# Analogread_final.net
KiCad netlist of a schematic drawn in Altium Designer
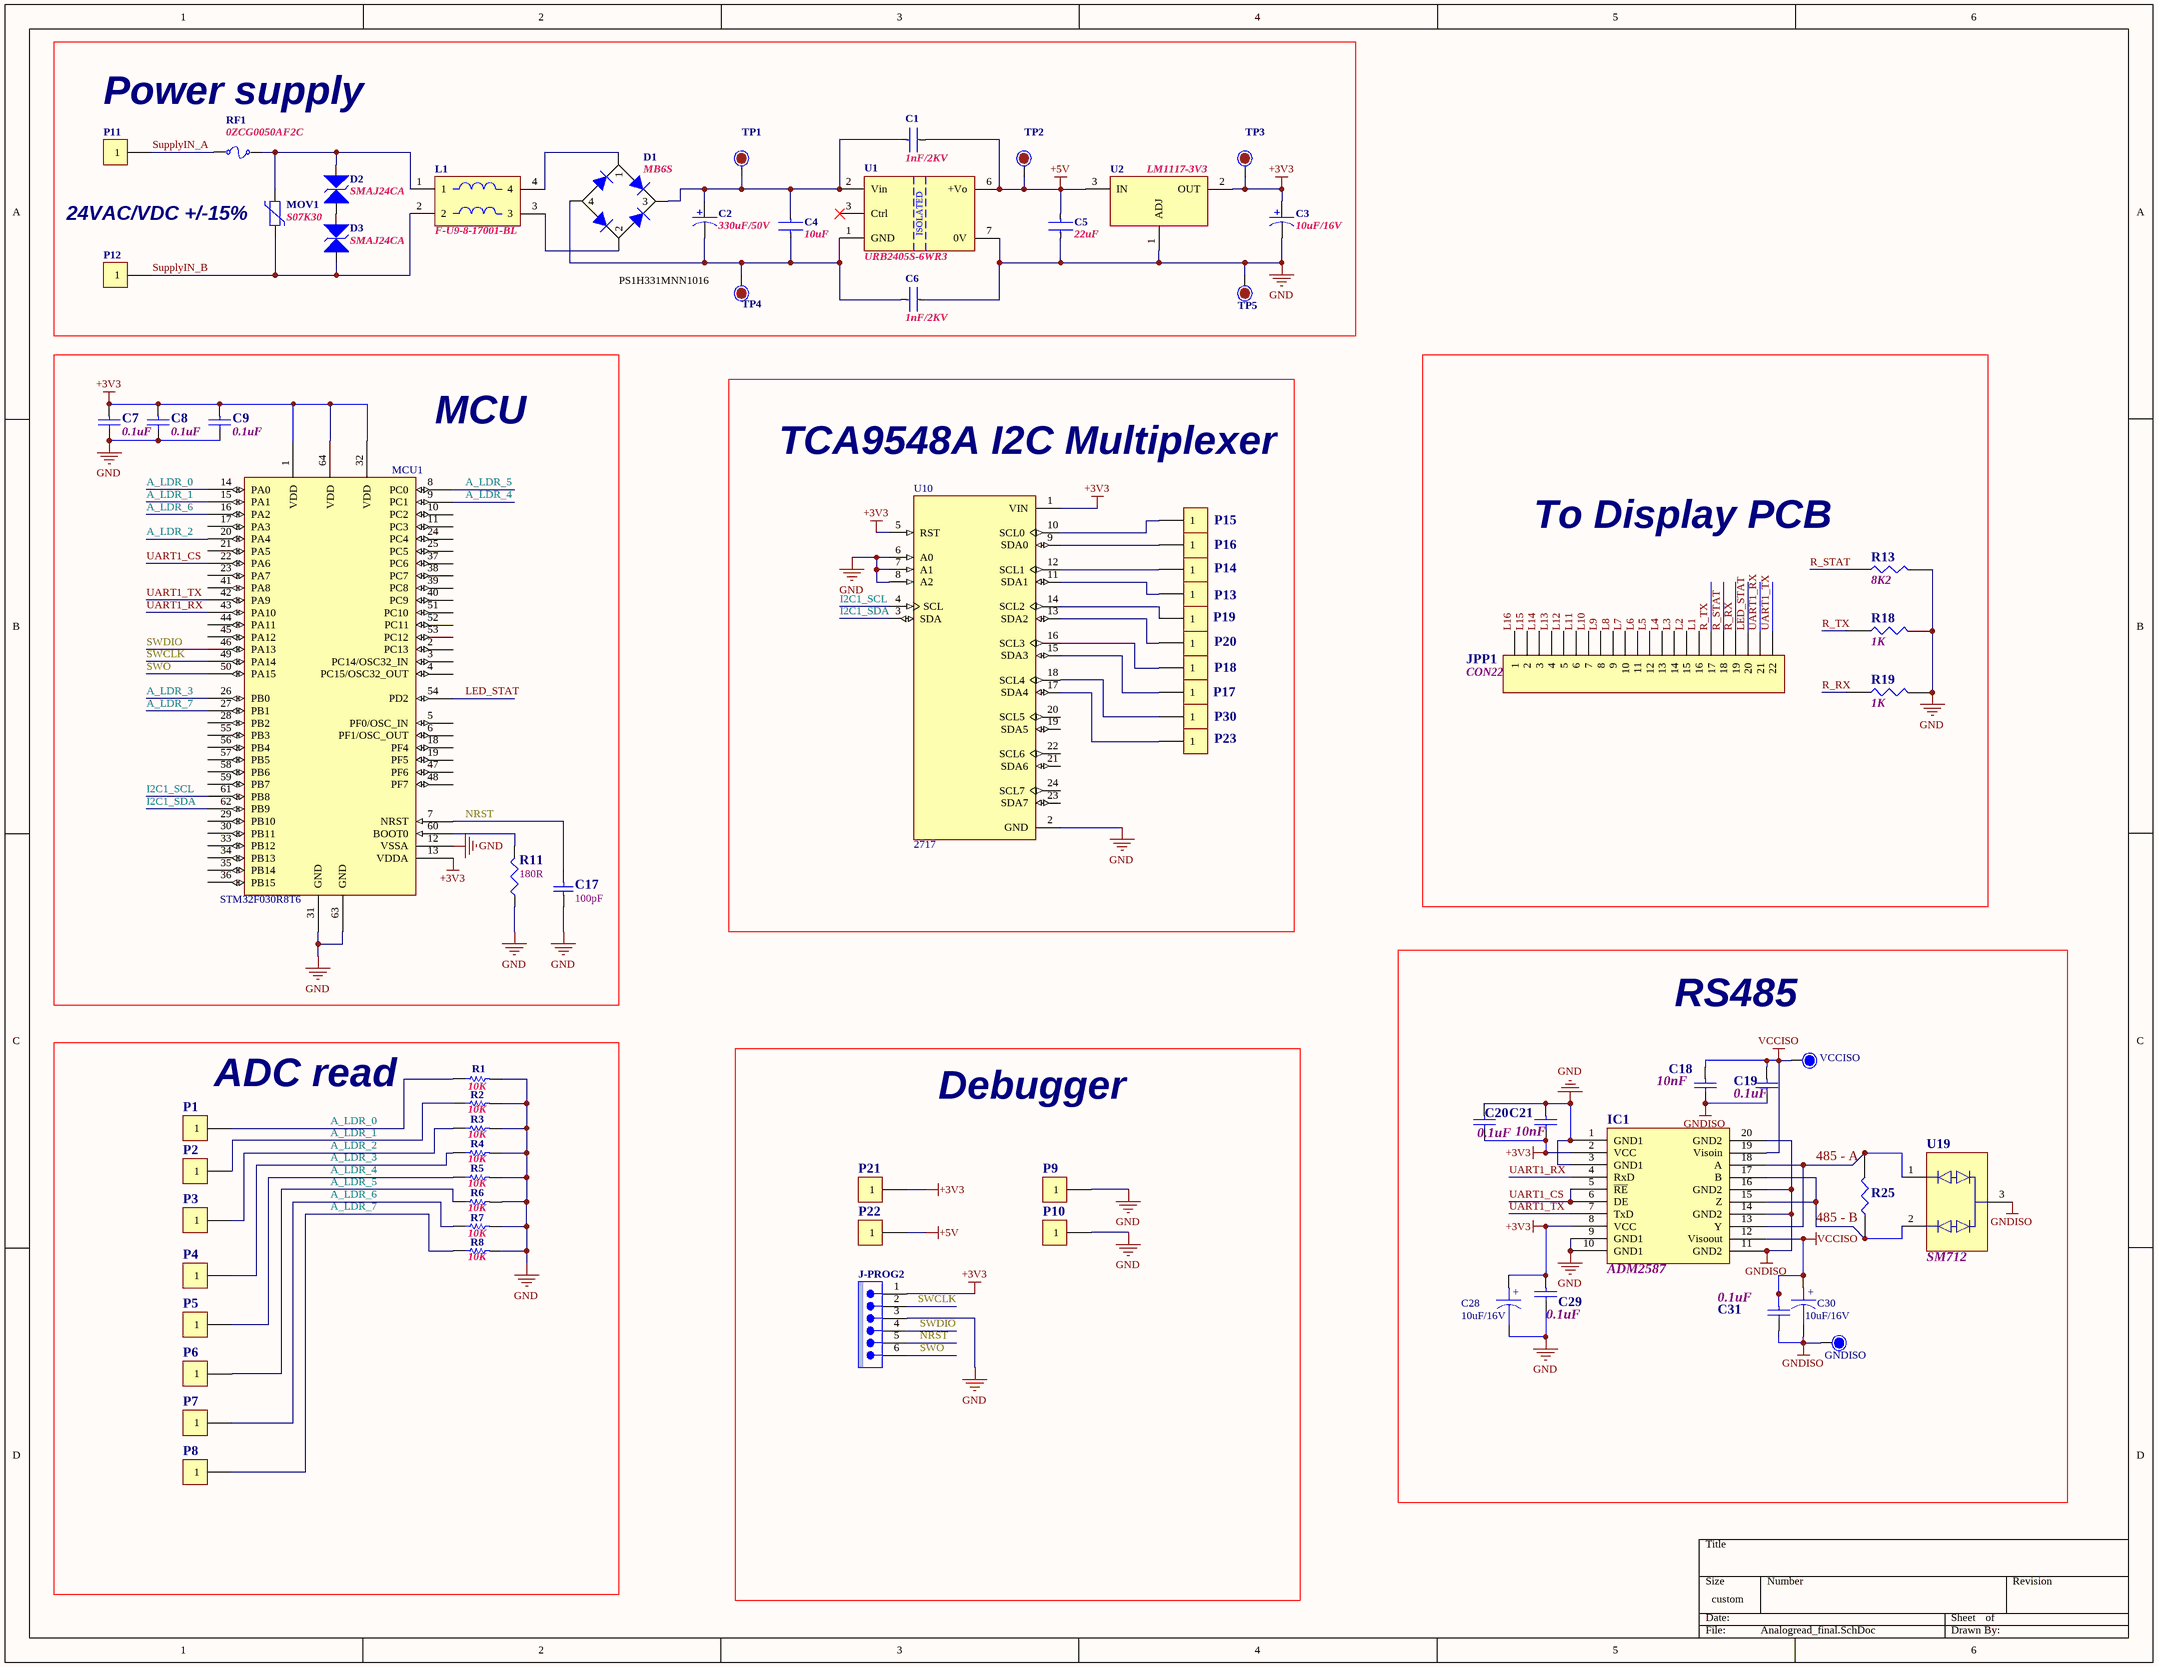
[diagram p0: Analogread_final.SchDoc]

(export (version "E")
  (design (tool "Eeschema 10.0.6"))
  (components
    (comp (ref "C1")
      (value "1nF/2KV")
      (footprint "CAPS0.3")
      (description "CAP CER, ?F, ?V, ?, THT 0.3\"")
      (libsource (lib "Primus") (part "CAP 0.3{dblquote} (THD)"))
    )
    (comp (ref "C2")
      (value "330uF/50V")
      (footprint "VER-D1000-H1250")
      (description "Aluminum Electrolytic Capacitor (Radial),\r\n?uF, ?V, Diameter 10mm")
      (libsource (lib "Primus") (part "CAP ELEC D10 (THD)"))
    )
    (comp (ref "C3")
      (value "10uF/16V")
      (footprint "CAPMP3528")
      (description "CAP TANTALUM, ?uF, ?V, 1411")
      (libsource (lib "Primus") (part "CAP TANTALUM (SMD)"))
    )
    (comp (ref "C4")
      (value "10uF")
      (footprint "CAPC2013 (0805)")
      (description "CAP CER, ?F, ?V, ±?%, 2013 (0805)")
      (libsource (lib "Primus") (part "CAP CHIP 0805 (SMD)"))
    )
    (comp (ref "C5")
      (value "22uF")
      (footprint "CAPC2013 (0805)")
      (description "CAP CER, ?F, ?V, ±?%, 2013 (0805)")
      (libsource (lib "Primus") (part "CAP CHIP 0805 (SMD)"))
    )
    (comp (ref "C6")
      (value "1nF/2KV")
      (footprint "CAPS0.3")
      (description "CAP CER, ?F, ?V, ?, THT 0.3\"")
      (libsource (lib "Primus") (part "CAP 0.3{dblquote} (THD)"))
    )
    (comp (ref "C7")
      (value "0.1uF")
      (footprint "CAPC1608 (0603)")
      (description "Capacitor")
      (libsource (lib "*") (part "CAP"))
    )
    (comp (ref "C8")
      (value "0.1uF")
      (footprint "CAPC1608 (0603)")
      (description "Capacitor")
      (libsource (lib "*") (part "CAP"))
    )
    (comp (ref "C9")
      (value "0.1uF")
      (footprint "CAPC1608 (0603)")
      (description "Capacitor")
      (libsource (lib "*") (part "CAP"))
    )
    (comp (ref "C17")
      (value "100pF")
      (footprint "CAPC1608 (0603)")
      (description "Capacitor")
      (fields (field (name "PUBLISHER") "Altium Limited"))
      (libsource (lib "*") (part "Cap"))
    )
    (comp (ref "C18")
      (value "10nF")
      (footprint "0805")
      (description "Capacitor")
      (libsource (lib "*") (part "CAP"))
    )
    (comp (ref "C19")
      (value "0.1uF")
      (footprint "CAPC1608 (0603)")
      (description "Capacitor")
      (libsource (lib "*") (part "CAP"))
    )
    (comp (ref "C20")
      (value "0.1uF")
      (footprint "CAPC1608 (0603)")
      (description "Capacitor")
      (libsource (lib "*") (part "CAP"))
    )
    (comp (ref "C21")
      (value "10nF")
      (footprint "0805")
      (description "Capacitor")
      (libsource (lib "*") (part "CAP"))
    )
    (comp (ref "C28")
      (value "10uF/16V")
      (footprint "CAPMP3528")
      (description "Capacitor")
      (libsource (lib "*") (part "CAPACITOR POL"))
    )
    (comp (ref "C29")
      (value "0.1uF")
      (footprint "CAPC1608 (0603)")
      (description "Capacitor")
      (libsource (lib "*") (part "CAP"))
    )
    (comp (ref "C30")
      (value "10uF/16V")
      (footprint "CAPMP3528")
      (description "Capacitor")
      (libsource (lib "*") (part "CAPACITOR POL"))
    )
    (comp (ref "C31")
      (value "0.1uF")
      (footprint "CAPC1608 (0603)")
      (description "Capacitor")
      (libsource (lib "*") (part "CAP"))
    )
    (comp (ref "D1") (value "MB6S") (footprint "MB6S") (libsource (lib "Primus") (part "MB6S")))
    (comp (ref "D2")
      (value "SMAJ24CA")
      (footprint "SMA-(DO-214AC)")
      (libsource (lib "Primus") (part "DIODE TVS BI-DIR"))
    )
    (comp (ref "D3")
      (value "SMAJ24CA")
      (footprint "SMA-(DO-214AC)")
      (libsource (lib "Primus") (part "DIODE TVS BI-DIR"))
    )
    (comp (ref "IC1")
      (value "ADM2587")
      (footprint "SOIC-20")
      (description "Transceiver with ±15 kV ESD Protection")
      (libsource (lib "Primus") (part "ADM2582E"))
    )
    (comp (ref "J-PROG2")
      (value "PIN HEADER 1x6")
      (footprint "PIN-HEADER 2.54 1x6")
      (libsource (lib "Primus") (part "PIN HEADER 1x6"))
    )
    (comp (ref "JPP1") (value "CON22") (footprint "JUMPER22") (libsource (lib "*") (part "CON22")))
    (comp (ref "L1")
      (value "F-U9-8-17001-BL")
      (footprint "BT-1720")
      (libsource (lib "Primus") (part "F-U9-8-17001-BL"))
    )
    (comp (ref "MCU1")
      (value "STM32F030R8T6")
      (footprint "QFP64 [10x10]")
      (libsource (lib "Primus") (part "STM32F030R8T6"))
    )
    (comp (ref "MOV1")
      (value "S07K30")
      (footprint "VARISTER(7MM)")
      (description "Disc Varistor 7mm")
      (libsource (lib "Primus") (part "Varistor D7"))
    )
    (comp (ref "P1")
      (value "CON1")
      (footprint "PAD_B3")
      (description "Connector")
      (libsource (lib "") (part "CON1_1"))
    )
    (comp (ref "P2")
      (value "CON1")
      (footprint "PAD_B3")
      (description "Connector")
      (libsource (lib "") (part "CON1_1"))
    )
    (comp (ref "P3")
      (value "CON1")
      (footprint "PAD_B3")
      (description "Connector")
      (libsource (lib "") (part "CON1_1"))
    )
    (comp (ref "P4")
      (value "CON1")
      (footprint "PAD_B3")
      (description "Connector")
      (libsource (lib "") (part "CON1_1"))
    )
    (comp (ref "P5")
      (value "CON1")
      (footprint "PAD_B3")
      (description "Connector")
      (libsource (lib "") (part "CON1_1"))
    )
    (comp (ref "P6")
      (value "CON1")
      (footprint "PAD_B3")
      (description "Connector")
      (libsource (lib "") (part "CON1_1"))
    )
    (comp (ref "P7")
      (value "CON1")
      (footprint "PAD_B3")
      (description "Connector")
      (libsource (lib "") (part "CON1_1"))
    )
    (comp (ref "P8")
      (value "CON1")
      (footprint "PAD_B3")
      (description "Connector")
      (libsource (lib "") (part "CON1_1"))
    )
    (comp (ref "P9")
      (value "CON1")
      (footprint "PAD_B3")
      (description "Connector")
      (libsource (lib "") (part "CON1_1"))
    )
    (comp (ref "P10")
      (value "CON1")
      (footprint "PAD_B3")
      (description "Connector")
      (libsource (lib "") (part "CON1_1"))
    )
    (comp (ref "P11") (value "1-PAD THT") (footprint "PAD-B3") (libsource (lib "Primus") (part "1-PAD THT")))
    (comp (ref "P12") (value "1-PAD THT") (footprint "PAD-B3") (libsource (lib "Primus") (part "1-PAD THT")))
    (comp (ref "P13")
      (value "CON1")
      (footprint "PAD_B3")
      (description "Connector")
      (libsource (lib "*") (part "CON1"))
    )
    (comp (ref "P14")
      (value "CON1")
      (footprint "PAD_B3")
      (description "Connector")
      (libsource (lib "*") (part "CON1"))
    )
    (comp (ref "P15")
      (value "CON1")
      (footprint "PAD_B3")
      (description "Connector")
      (libsource (lib "*") (part "CON1"))
    )
    (comp (ref "P16")
      (value "CON1")
      (footprint "PAD_B3")
      (description "Connector")
      (libsource (lib "*") (part "CON1"))
    )
    (comp (ref "P17")
      (value "CON1")
      (footprint "PAD_B3")
      (description "Connector")
      (libsource (lib "*") (part "CON1"))
    )
    (comp (ref "P18")
      (value "CON1")
      (footprint "PAD_B3")
      (description "Connector")
      (libsource (lib "*") (part "CON1"))
    )
    (comp (ref "P19")
      (value "CON1")
      (footprint "PAD_B3")
      (description "Connector")
      (libsource (lib "*") (part "CON1"))
    )
    (comp (ref "P20")
      (value "CON1")
      (footprint "PAD_B3")
      (description "Connector")
      (libsource (lib "*") (part "CON1"))
    )
    (comp (ref "P21")
      (value "CON1")
      (footprint "PAD_B3")
      (description "Connector")
      (libsource (lib "") (part "CON1_1"))
    )
    (comp (ref "P22")
      (value "CON1")
      (footprint "PAD_B3")
      (description "Connector")
      (libsource (lib "") (part "CON1_1"))
    )
    (comp (ref "P23")
      (value "CON1")
      (footprint "PAD_B3")
      (description "Connector")
      (libsource (lib "*") (part "CON1"))
    )
    (comp (ref "P30")
      (value "CON1")
      (footprint "PAD_B3")
      (description "Connector")
      (libsource (lib "*") (part "CON1"))
    )
    (comp (ref "R1")
      (value "10K")
      (footprint "RESC1608 (0603)")
      (description "Chip Resistor, ? Ohm, +/-?%, ?W, 1608 (0603)")
      (libsource (lib "Primus") (part "RES CHIP 0603 (SMD)"))
    )
    (comp (ref "R2")
      (value "10K")
      (footprint "RESC1608 (0603)")
      (description "Chip Resistor, ? Ohm, +/-?%, ?W, 1608 (0603)")
      (libsource (lib "Primus") (part "RES CHIP 0603 (SMD)"))
    )
    (comp (ref "R3")
      (value "10K")
      (footprint "RESC1608 (0603)")
      (description "Chip Resistor, ? Ohm, +/-?%, ?W, 1608 (0603)")
      (libsource (lib "Primus") (part "RES CHIP 0603 (SMD)"))
    )
    (comp (ref "R4")
      (value "10K")
      (footprint "RESC1608 (0603)")
      (description "Chip Resistor, ? Ohm, +/-?%, ?W, 1608 (0603)")
      (libsource (lib "Primus") (part "RES CHIP 0603 (SMD)"))
    )
    (comp (ref "R5")
      (value "10K")
      (footprint "RESC1608 (0603)")
      (description "Chip Resistor, ? Ohm, +/-?%, ?W, 1608 (0603)")
      (libsource (lib "Primus") (part "RES CHIP 0603 (SMD)"))
    )
    (comp (ref "R6")
      (value "10K")
      (footprint "RESC1608 (0603)")
      (description "Chip Resistor, ? Ohm, +/-?%, ?W, 1608 (0603)")
      (libsource (lib "Primus") (part "RES CHIP 0603 (SMD)"))
    )
    (comp (ref "R7")
      (value "10K")
      (footprint "RESC1608 (0603)")
      (description "Chip Resistor, ? Ohm, +/-?%, ?W, 1608 (0603)")
      (libsource (lib "Primus") (part "RES CHIP 0603 (SMD)"))
    )
    (comp (ref "R8")
      (value "10K")
      (footprint "RESC1608 (0603)")
      (description "Chip Resistor, ? Ohm, +/-?%, ?W, 1608 (0603)")
      (libsource (lib "Primus") (part "RES CHIP 0603 (SMD)"))
    )
    (comp (ref "R11")
      (value "180R")
      (footprint "0805")
      (description "Resistor")
      (fields (field (name "PUBLISHER") "Altium Limited"))
      (libsource (lib "*") (part "Res3"))
    )
    (comp (ref "R13") (value "8K2") (footprint "RESC1608 (0603)") (libsource (lib "*") (part "RES1")))
    (comp (ref "R18") (value "1K") (footprint "RESC1608 (0603)") (libsource (lib "*") (part "RES1")))
    (comp (ref "R19") (value "1K") (footprint "RESC1608 (0603)") (libsource (lib "*") (part "RES1")))
    (comp (ref "R25") (value "~") (footprint "0805") (libsource (lib "*") (part "RES1")))
    (comp (ref "RF1")
      (value "0ZCG0050AF2C")
      (footprint "0ZCGXXXXXXXX")
      (description "Polymeric PTC Resettable Fuse 30V 500 mA Ih Surface Mount 1812 (4532 Metric), Concave")
      (libsource (lib "Primus") (part "0ZCG0050AF2C"))
    )
    (comp (ref "TP1")
      (value "+VIN")
      (footprint "TP1-1.2mm")
      (description "TEST PAD")
      (libsource (lib "Primus") (part "TP"))
    )
    (comp (ref "TP2")
      (value "+5V")
      (footprint "TP1-1.2mm")
      (description "TEST PAD")
      (libsource (lib "Primus") (part "TP"))
    )
    (comp (ref "TP3")
      (value "+3V3")
      (footprint "TP1-1.2mm")
      (description "TEST PAD")
      (libsource (lib "Primus") (part "TP"))
    )
    (comp (ref "TP4")
      (value "G_VIN")
      (footprint "TP1-1.2mm")
      (description "TEST PAD")
      (libsource (lib "Primus") (part "TP"))
    )
    (comp (ref "TP5")
      (value "GND")
      (footprint "TP1-1.2mm")
      (description "TEST PAD")
      (libsource (lib "Primus") (part "TP"))
    )
    (comp (ref "TP6")
      (value "VCCISO")
      (footprint "TP1-1.2mm")
      (description "TEST PAD")
      (libsource (lib "Primus") (part "TP"))
    )
    (comp (ref "TP7")
      (value "GNDISO")
      (footprint "TP1-1.2mm")
      (description "TEST PAD")
      (libsource (lib "Primus") (part "TP"))
    )
    (comp (ref "U1")
      (value "URB2405S-6WR3")
      (footprint "URBxxxxS-6WR3")
      (description "6W, Regulated, Isolated, DC to DC Converter,\r\n24V to 5V@1200mA")
      (libsource (lib "Primus") (part "URB2405S-6WR3"))
    )
    (comp (ref "U2")
      (value "LM1117-3V3")
      (footprint "SOT-223")
      (description "Low-Dropout Linear Regulator 800 mA")
      (libsource (lib "Primus") (part "LM1117-3V3"))
    )
    (comp (ref "U10")
      (value "2717")
      (footprint "MODULE_2717")
      (description "Module: multiplexer; I2C interface multiplexer; TCA9548A; 3Ã·5VDC")
      (fields (field (name "MF") "Adafruit"))
      (libsource (lib "2717") (part "2717"))
    )
    (comp (ref "U19") (value "SM712") (footprint "SOT-23-3") (libsource (lib "*") (part "SM712")))
  )
  (nets
    (net (code "1") (name "+3V3") (class "Default")
      (node (ref "C20") (pin "2") (pinfunction "2_2") (pintype "passive"))
      (node (ref "C21") (pin "2") (pinfunction "2_2") (pintype "passive"))
      (node (ref "C28") (pin "1") (pinfunction "1_1") (pintype "passive"))
      (node (ref "C29") (pin "1") (pinfunction "1_1") (pintype "passive"))
      (node (ref "C3") (pin "1") (pinfunction "1_1") (pintype "passive"))
      (node (ref "C7") (pin "1") (pinfunction "1_1") (pintype "passive"))
      (node (ref "C8") (pin "1") (pinfunction "1_1") (pintype "passive"))
      (node (ref "C9") (pin "1") (pinfunction "1_1") (pintype "passive"))
      (node (ref "IC1") (pin "2") (pinfunction "VCC_2") (pintype "passive"))
      (node (ref "IC1") (pin "8") (pinfunction "VCC_8") (pintype "passive"))
      (node (ref "J-PROG2") (pin "1") (pinfunction "1_1") (pintype "passive"))
      (node (ref "MCU1") (pin "1") (pinfunction "VDD_1") (pintype "passive"))
      (node (ref "MCU1") (pin "13") (pinfunction "VDDA_13") (pintype "power_in"))
      (node (ref "MCU1") (pin "32") (pinfunction "VDD_32") (pintype "passive"))
      (node (ref "MCU1") (pin "64") (pinfunction "VDD_64") (pintype "passive"))
      (node (ref "P21") (pin "1") (pinfunction "1_1") (pintype "passive"))
      (node (ref "TP3") (pin "TP") (pinfunction "Test_point_TP") (pintype "passive"))
      (node (ref "U10") (pin "1") (pinfunction "VIN_1") (pintype "power_in"))
      (node (ref "U10") (pin "5") (pinfunction "RST_5") (pintype "input"))
      (node (ref "U2") (pin "2") (pinfunction "OUT_2") (pintype "passive"))
    )
    (net (code "2") (name "+5V") (class "Default")
      (node (ref "C1") (pin "2") (pinfunction "2_2") (pintype "passive"))
      (node (ref "C5") (pin "2") (pinfunction "2_2") (pintype "passive"))
      (node (ref "P22") (pin "1") (pinfunction "1_1") (pintype "passive"))
      (node (ref "TP2") (pin "TP") (pinfunction "Test_point_TP") (pintype "passive"))
      (node (ref "U1") (pin "6") (pinfunction "+Vo_6") (pintype "passive"))
      (node (ref "U2") (pin "3") (pinfunction "IN_3") (pintype "passive"))
    )
    (net (code "3") (name "/485 - A") (class "Default")
      (node (ref "IC1") (pin "13") (pinfunction "Y_13") (pintype "passive"))
      (node (ref "IC1") (pin "18") (pinfunction "A_18") (pintype "passive"))
      (node (ref "R25") (pin "2") (pinfunction "2_2") (pintype "passive"))
      (node (ref "U19") (pin "1") (pinfunction "1_1") (pintype "passive"))
    )
    (net (code "4") (name "/485 - B") (class "Default")
      (node (ref "IC1") (pin "15") (pinfunction "Z_15") (pintype "passive"))
      (node (ref "IC1") (pin "17") (pinfunction "B_17") (pintype "passive"))
      (node (ref "R25") (pin "1") (pinfunction "1_1") (pintype "passive"))
      (node (ref "U19") (pin "2") (pinfunction "2_2") (pintype "passive"))
    )
    (net (code "5") (name "/A_LDR_0") (class "Default")
      (node (ref "MCU1") (pin "14") (pinfunction "PA0_14") (pintype "bidirectional"))
      (node (ref "P1") (pin "1") (pinfunction "1_1") (pintype "passive"))
      (node (ref "R1") (pin "2") (pinfunction "13_2") (pintype "passive"))
    )
    (net (code "6") (name "/A_LDR_1") (class "Default")
      (node (ref "MCU1") (pin "15") (pinfunction "PA1_15") (pintype "bidirectional"))
      (node (ref "P2") (pin "1") (pinfunction "1_1") (pintype "passive"))
      (node (ref "R2") (pin "2") (pinfunction "13_2") (pintype "passive"))
    )
    (net (code "7") (name "/A_LDR_2") (class "Default")
      (node (ref "MCU1") (pin "20") (pinfunction "PA4_20") (pintype "bidirectional"))
      (node (ref "P3") (pin "1") (pinfunction "1_1") (pintype "passive"))
      (node (ref "R3") (pin "2") (pinfunction "13_2") (pintype "passive"))
    )
    (net (code "8") (name "/A_LDR_3") (class "Default")
      (node (ref "MCU1") (pin "26") (pinfunction "PB0_26") (pintype "bidirectional"))
      (node (ref "P4") (pin "1") (pinfunction "1_1") (pintype "passive"))
      (node (ref "R4") (pin "2") (pinfunction "13_2") (pintype "passive"))
    )
    (net (code "9") (name "/A_LDR_4") (class "Default")
      (node (ref "MCU1") (pin "9") (pinfunction "PC1_9") (pintype "bidirectional"))
      (node (ref "P5") (pin "1") (pinfunction "1_1") (pintype "passive"))
      (node (ref "R5") (pin "2") (pinfunction "13_2") (pintype "passive"))
    )
    (net (code "10") (name "/A_LDR_5") (class "Default")
      (node (ref "MCU1") (pin "8") (pinfunction "PC0_8") (pintype "bidirectional"))
      (node (ref "P6") (pin "1") (pinfunction "1_1") (pintype "passive"))
      (node (ref "R6") (pin "2") (pinfunction "13_2") (pintype "passive"))
    )
    (net (code "11") (name "/A_LDR_6") (class "Default")
      (node (ref "MCU1") (pin "16") (pinfunction "PA2_16") (pintype "bidirectional"))
      (node (ref "P7") (pin "1") (pinfunction "1_1") (pintype "passive"))
      (node (ref "R7") (pin "2") (pinfunction "13_2") (pintype "passive"))
    )
    (net (code "12") (name "/A_LDR_7") (class "Default")
      (node (ref "MCU1") (pin "27") (pinfunction "PB1_27") (pintype "bidirectional"))
      (node (ref "P8") (pin "1") (pinfunction "1_1") (pintype "passive"))
      (node (ref "R8") (pin "2") (pinfunction "13_2") (pintype "passive"))
    )
    (net (code "13") (name "/I2C1_SCL") (class "Default")
      (node (ref "MCU1") (pin "61") (pinfunction "PB8_61") (pintype "bidirectional"))
      (node (ref "U10") (pin "4") (pinfunction "SCL_4") (pintype "input"))
    )
    (net (code "14") (name "/I2C1_SDA") (class "Default")
      (node (ref "MCU1") (pin "62") (pinfunction "PB9_62") (pintype "bidirectional"))
      (node (ref "U10") (pin "3") (pinfunction "SDA_3") (pintype "bidirectional"))
    )
    (net (code "15") (name "/L1") (class "Default")
      (node (ref "JPP1") (pin "16") (pinfunction "16_16") (pintype "passive"))
    )
    (net (code "16") (name "/L2") (class "Default")
      (node (ref "JPP1") (pin "15") (pinfunction "15_15") (pintype "passive"))
    )
    (net (code "17") (name "/L3") (class "Default")
      (node (ref "JPP1") (pin "14") (pinfunction "14_14") (pintype "passive"))
    )
    (net (code "18") (name "/L4") (class "Default")
      (node (ref "JPP1") (pin "13") (pinfunction "13_13") (pintype "passive"))
    )
    (net (code "19") (name "/L5") (class "Default")
      (node (ref "JPP1") (pin "12") (pinfunction "12_12") (pintype "passive"))
    )
    (net (code "20") (name "/L6") (class "Default")
      (node (ref "JPP1") (pin "11") (pinfunction "11_11") (pintype "passive"))
    )
    (net (code "21") (name "/L7") (class "Default")
      (node (ref "JPP1") (pin "10") (pinfunction "10_10") (pintype "passive"))
    )
    (net (code "22") (name "/L8") (class "Default")
      (node (ref "JPP1") (pin "9") (pinfunction "9_9") (pintype "passive"))
    )
    (net (code "23") (name "/L9") (class "Default")
      (node (ref "JPP1") (pin "8") (pinfunction "8_8") (pintype "passive"))
    )
    (net (code "24") (name "/L10") (class "Default")
      (node (ref "JPP1") (pin "7") (pinfunction "7_7") (pintype "passive"))
    )
    (net (code "25") (name "/L11") (class "Default")
      (node (ref "JPP1") (pin "6") (pinfunction "6_6") (pintype "passive"))
    )
    (net (code "26") (name "/L12") (class "Default")
      (node (ref "JPP1") (pin "5") (pinfunction "5_5") (pintype "passive"))
    )
    (net (code "27") (name "/L13") (class "Default")
      (node (ref "JPP1") (pin "4") (pinfunction "4_4") (pintype "passive"))
    )
    (net (code "28") (name "/L14") (class "Default")
      (node (ref "JPP1") (pin "3") (pinfunction "3_3") (pintype "passive"))
    )
    (net (code "29") (name "/L15") (class "Default")
      (node (ref "JPP1") (pin "2") (pinfunction "2_2") (pintype "passive"))
    )
    (net (code "30") (name "/L16") (class "Default")
      (node (ref "JPP1") (pin "1") (pinfunction "1_1") (pintype "passive"))
    )
    (net (code "31") (name "/LED_STAT") (class "Default")
      (node (ref "JPP1") (pin "20") (pinfunction "20_20") (pintype "passive"))
      (node (ref "MCU1") (pin "54") (pinfunction "PD2_54") (pintype "bidirectional"))
    )
    (net (code "32") (name "/NRST") (class "Default")
      (node (ref "C17") (pin "2") (pinfunction "2_2") (pintype "passive"))
      (node (ref "J-PROG2") (pin "5") (pinfunction "5_5") (pintype "passive"))
      (node (ref "MCU1") (pin "7") (pinfunction "NRST_7") (pintype "input"))
    )
    (net (code "33") (name "/R_RX") (class "Default")
      (node (ref "JPP1") (pin "19") (pinfunction "19_19") (pintype "passive"))
      (node (ref "R19") (pin "1") (pinfunction "1_1") (pintype "passive"))
    )
    (net (code "34") (name "/R_STAT") (class "Default")
      (node (ref "JPP1") (pin "18") (pinfunction "18_18") (pintype "passive"))
      (node (ref "R13") (pin "1") (pinfunction "1_1") (pintype "passive"))
    )
    (net (code "35") (name "/R_TX") (class "Default")
      (node (ref "JPP1") (pin "17") (pinfunction "17_17") (pintype "passive"))
      (node (ref "R18") (pin "1") (pinfunction "1_1") (pintype "passive"))
    )
    (net (code "36") (name "/SWCLK") (class "Default")
      (node (ref "J-PROG2") (pin "2") (pinfunction "2_2") (pintype "passive"))
      (node (ref "MCU1") (pin "49") (pinfunction "PA14_49") (pintype "bidirectional"))
    )
    (net (code "37") (name "/SWDIO") (class "Default")
      (node (ref "J-PROG2") (pin "4") (pinfunction "4_4") (pintype "passive"))
      (node (ref "MCU1") (pin "46") (pinfunction "PA13_46") (pintype "bidirectional"))
    )
    (net (code "38") (name "/SWO") (class "Default")
      (node (ref "J-PROG2") (pin "6") (pinfunction "6_6") (pintype "passive"))
      (node (ref "MCU1") (pin "50") (pinfunction "PA15_50") (pintype "bidirectional"))
    )
    (net (code "39") (name "/SupplyIN_A") (class "Default")
      (node (ref "P11") (pin "1") (pinfunction "1_1") (pintype "passive"))
      (node (ref "RF1") (pin "1") (pinfunction "1_1") (pintype "passive"))
    )
    (net (code "40") (name "/SupplyIN_B") (class "Default")
      (node (ref "D3") (pin "A") (pinfunction "A_A") (pintype "passive"))
      (node (ref "L1") (pin "2") (pinfunction "2_2") (pintype "passive"))
      (node (ref "MOV1") (pin "2") (pinfunction "2_2") (pintype "passive"))
      (node (ref "P12") (pin "1") (pinfunction "1_1") (pintype "passive"))
    )
    (net (code "41") (name "/UART1_CS") (class "Default")
      (node (ref "IC1") (pin "5") (pinfunction "~{RE}_5") (pintype "passive"))
      (node (ref "IC1") (pin "6") (pinfunction "DE_6") (pintype "passive"))
      (node (ref "MCU1") (pin "22") (pinfunction "PA6_22") (pintype "bidirectional"))
    )
    (net (code "42") (name "/UART1_RX") (class "Default")
      (node (ref "IC1") (pin "4") (pinfunction "RxD_4") (pintype "passive"))
      (node (ref "JPP1") (pin "21") (pinfunction "21_21") (pintype "passive"))
      (node (ref "MCU1") (pin "43") (pinfunction "PA10_43") (pintype "bidirectional"))
    )
    (net (code "43") (name "/UART1_TX") (class "Default")
      (node (ref "IC1") (pin "7") (pinfunction "TxD_7") (pintype "passive"))
      (node (ref "JPP1") (pin "22") (pinfunction "22_22") (pintype "passive"))
      (node (ref "MCU1") (pin "42") (pinfunction "PA9_42") (pintype "bidirectional"))
    )
    (net (code "44") (name "GND") (class "Default")
      (node (ref "C17") (pin "1") (pinfunction "1_1") (pintype "passive"))
      (node (ref "C20") (pin "1") (pinfunction "1_1") (pintype "passive"))
      (node (ref "C21") (pin "1") (pinfunction "1_1") (pintype "passive"))
      (node (ref "C28") (pin "2") (pinfunction "2_2") (pintype "passive"))
      (node (ref "C29") (pin "2") (pinfunction "2_2") (pintype "passive"))
      (node (ref "C3") (pin "2") (pinfunction "2_2") (pintype "passive"))
      (node (ref "C5") (pin "1") (pinfunction "1_1") (pintype "passive"))
      (node (ref "C6") (pin "2") (pinfunction "2_2") (pintype "passive"))
      (node (ref "C7") (pin "2") (pinfunction "2_2") (pintype "passive"))
      (node (ref "C8") (pin "2") (pinfunction "2_2") (pintype "passive"))
      (node (ref "C9") (pin "2") (pinfunction "2_2") (pintype "passive"))
      (node (ref "IC1") (pin "1") (pinfunction "GND1_1") (pintype "passive"))
      (node (ref "IC1") (pin "10") (pinfunction "GND1_10") (pintype "passive"))
      (node (ref "IC1") (pin "3") (pinfunction "GND1_3") (pintype "passive"))
      (node (ref "IC1") (pin "9") (pinfunction "GND1_9") (pintype "passive"))
      (node (ref "J-PROG2") (pin "3") (pinfunction "3_3") (pintype "passive"))
      (node (ref "MCU1") (pin "12") (pinfunction "VSSA_12") (pintype "power_in"))
      (node (ref "MCU1") (pin "31") (pinfunction "GND_31") (pintype "passive"))
      (node (ref "MCU1") (pin "63") (pinfunction "GND_63") (pintype "passive"))
      (node (ref "P10") (pin "1") (pinfunction "1_1") (pintype "passive"))
      (node (ref "P9") (pin "1") (pinfunction "1_1") (pintype "passive"))
      (node (ref "R1") (pin "1") (pinfunction "12_1") (pintype "passive"))
      (node (ref "R11") (pin "1") (pinfunction "1_1") (pintype "passive"))
      (node (ref "R13") (pin "2") (pinfunction "2_2") (pintype "passive"))
      (node (ref "R18") (pin "2") (pinfunction "2_2") (pintype "passive"))
      (node (ref "R19") (pin "2") (pinfunction "2_2") (pintype "passive"))
      (node (ref "R2") (pin "1") (pinfunction "12_1") (pintype "passive"))
      (node (ref "R3") (pin "1") (pinfunction "12_1") (pintype "passive"))
      (node (ref "R4") (pin "1") (pinfunction "12_1") (pintype "passive"))
      (node (ref "R5") (pin "1") (pinfunction "12_1") (pintype "passive"))
      (node (ref "R6") (pin "1") (pinfunction "12_1") (pintype "passive"))
      (node (ref "R7") (pin "1") (pinfunction "12_1") (pintype "passive"))
      (node (ref "R8") (pin "1") (pinfunction "12_1") (pintype "passive"))
      (node (ref "TP5") (pin "TP") (pinfunction "Test_point_TP") (pintype "passive"))
      (node (ref "U1") (pin "7") (pinfunction "0V_7") (pintype "passive"))
      (node (ref "U10") (pin "2") (pinfunction "GND_2") (pintype "power_in"))
      (node (ref "U10") (pin "6") (pinfunction "A0_6") (pintype "input"))
      (node (ref "U10") (pin "7") (pinfunction "A1_7") (pintype "input"))
      (node (ref "U10") (pin "8") (pinfunction "A2_8") (pintype "input"))
      (node (ref "U2") (pin "1") (pinfunction "ADJ_1") (pintype "passive"))
    )
    (net (code "45") (name "GNDISO") (class "Default")
      (node (ref "C18") (pin "2") (pinfunction "2_2") (pintype "passive"))
      (node (ref "C19") (pin "2") (pinfunction "2_2") (pintype "passive"))
      (node (ref "C30") (pin "2") (pinfunction "2_2") (pintype "passive"))
      (node (ref "C31") (pin "2") (pinfunction "2_2") (pintype "passive"))
      (node (ref "IC1") (pin "11") (pinfunction "GND2_11") (pintype "passive"))
      (node (ref "IC1") (pin "14") (pinfunction "GND2_14") (pintype "passive"))
      (node (ref "IC1") (pin "16") (pinfunction "GND2_16") (pintype "passive"))
      (node (ref "IC1") (pin "20") (pinfunction "GND2_20") (pintype "passive"))
      (node (ref "TP7") (pin "TP") (pinfunction "Test_point_TP") (pintype "passive"))
      (node (ref "U19") (pin "3") (pinfunction "3_3") (pintype "passive"))
    )
    (net (code "46") (name "Net-(D1-Pad1)") (class "Default")
      (node (ref "D1") (pin "1") (pinfunction "1_1") (pintype "passive"))
      (node (ref "L1") (pin "4") (pinfunction "4_4") (pintype "passive"))
    )
    (net (code "47") (name "Net-(D1-Pad2)") (class "Default")
      (node (ref "D1") (pin "2") (pinfunction "2_2") (pintype "passive"))
      (node (ref "L1") (pin "3") (pinfunction "3_3") (pintype "passive"))
    )
    (net (code "48") (name "Net-(D2-PadA)") (class "Default")
      (node (ref "D2") (pin "A") (pinfunction "A_A") (pintype "passive"))
      (node (ref "D3") (pin "C") (pinfunction "C_C") (pintype "passive"))
    )
    (net (code "49") (name "Net-(D2-PadC)") (class "Default")
      (node (ref "D2") (pin "C") (pinfunction "C_C") (pintype "passive"))
      (node (ref "L1") (pin "1") (pinfunction "1_1") (pintype "passive"))
      (node (ref "MOV1") (pin "1") (pinfunction "1_1") (pintype "passive"))
      (node (ref "RF1") (pin "2") (pinfunction "2_2") (pintype "passive"))
    )
    (net (code "50") (name "Net-(MCU1-BOOT0)") (class "Default")
      (node (ref "MCU1") (pin "60") (pinfunction "BOOT0_60") (pintype "input"))
      (node (ref "R11") (pin "2") (pinfunction "2_2") (pintype "passive"))
    )
    (net (code "51") (name "Net-(TP1-Test_point)") (class "Default")
      (node (ref "C1") (pin "1") (pinfunction "1_1") (pintype "passive"))
      (node (ref "C2") (pin "1") (pinfunction "1_1") (pintype "passive"))
      (node (ref "C4") (pin "2") (pinfunction "2_2") (pintype "passive"))
      (node (ref "D1") (pin "3") (pinfunction "3_3") (pintype "passive"))
      (node (ref "TP1") (pin "TP") (pinfunction "Test_point_TP") (pintype "passive"))
      (node (ref "U1") (pin "2") (pinfunction "Vin_2") (pintype "passive"))
    )
    (net (code "52") (name "Net-(TP4-Test_point)") (class "Default")
      (node (ref "C2") (pin "2") (pinfunction "2_2") (pintype "passive"))
      (node (ref "C4") (pin "1") (pinfunction "1_1") (pintype "passive"))
      (node (ref "C6") (pin "1") (pinfunction "1_1") (pintype "passive"))
      (node (ref "D1") (pin "4") (pinfunction "4_4") (pintype "passive"))
      (node (ref "TP4") (pin "TP") (pinfunction "Test_point_TP") (pintype "passive"))
      (node (ref "U1") (pin "1") (pinfunction "GND_1") (pintype "passive"))
    )
    (net (code "53") (name "Net-(U10-SCL0)") (class "Default")
      (node (ref "P15") (pin "1") (pinfunction "1_1") (pintype "passive"))
      (node (ref "U10") (pin "10") (pinfunction "SCL0_10") (pintype "output"))
    )
    (net (code "54") (name "Net-(U10-SCL1)") (class "Default")
      (node (ref "P14") (pin "1") (pinfunction "1_1") (pintype "passive"))
      (node (ref "U10") (pin "12") (pinfunction "SCL1_12") (pintype "output"))
    )
    (net (code "55") (name "Net-(U10-SCL2)") (class "Default")
      (node (ref "P19") (pin "1") (pinfunction "1_1") (pintype "passive"))
      (node (ref "U10") (pin "14") (pinfunction "SCL2_14") (pintype "output"))
    )
    (net (code "56") (name "Net-(U10-SCL3)") (class "Default")
      (node (ref "P18") (pin "1") (pinfunction "1_1") (pintype "passive"))
      (node (ref "U10") (pin "16") (pinfunction "SCL3_16") (pintype "output"))
    )
    (net (code "57") (name "Net-(U10-SCL4)") (class "Default")
      (node (ref "P30") (pin "1") (pinfunction "1_1") (pintype "passive"))
      (node (ref "U10") (pin "18") (pinfunction "SCL4_18") (pintype "output"))
    )
    (net (code "58") (name "Net-(U10-SDA0)") (class "Default")
      (node (ref "P16") (pin "1") (pinfunction "1_1") (pintype "passive"))
      (node (ref "U10") (pin "9") (pinfunction "SDA0_9") (pintype "bidirectional"))
    )
    (net (code "59") (name "Net-(U10-SDA1)") (class "Default")
      (node (ref "P13") (pin "1") (pinfunction "1_1") (pintype "passive"))
      (node (ref "U10") (pin "11") (pinfunction "SDA1_11") (pintype "bidirectional"))
    )
    (net (code "60") (name "Net-(U10-SDA2)") (class "Default")
      (node (ref "P20") (pin "1") (pinfunction "1_1") (pintype "passive"))
      (node (ref "U10") (pin "13") (pinfunction "SDA2_13") (pintype "bidirectional"))
    )
    (net (code "61") (name "Net-(U10-SDA3)") (class "Default")
      (node (ref "P17") (pin "1") (pinfunction "1_1") (pintype "passive"))
      (node (ref "U10") (pin "15") (pinfunction "SDA3_15") (pintype "bidirectional"))
    )
    (net (code "62") (name "Net-(U10-SDA4)") (class "Default")
      (node (ref "P23") (pin "1") (pinfunction "1_1") (pintype "passive"))
      (node (ref "U10") (pin "17") (pinfunction "SDA4_17") (pintype "bidirectional"))
    )
    (net (code "63") (name "VCCISO") (class "Default")
      (node (ref "C18") (pin "1") (pinfunction "1_1") (pintype "passive"))
      (node (ref "C19") (pin "1") (pinfunction "1_1") (pintype "passive"))
      (node (ref "C30") (pin "1") (pinfunction "1_1") (pintype "passive"))
      (node (ref "C31") (pin "1") (pinfunction "1_1") (pintype "passive"))
      (node (ref "IC1") (pin "12") (pinfunction "Visoout_12") (pintype "passive"))
      (node (ref "IC1") (pin "19") (pinfunction "Visoin_19") (pintype "passive"))
      (node (ref "TP6") (pin "TP") (pinfunction "Test_point_TP") (pintype "passive"))
    )
    (net (code "64") (name "unconnected-(MCU1-PA3-Pad17)") (class "Default")
      (node (ref "MCU1") (pin "17") (pinfunction "PA3_17") (pintype "bidirectional"))
    )
    (net (code "65") (name "unconnected-(MCU1-PA5-Pad21)") (class "Default")
      (node (ref "MCU1") (pin "21") (pinfunction "PA5_21") (pintype "bidirectional"))
    )
    (net (code "66") (name "unconnected-(MCU1-PA7-Pad23)") (class "Default")
      (node (ref "MCU1") (pin "23") (pinfunction "PA7_23") (pintype "bidirectional"))
    )
    (net (code "67") (name "unconnected-(MCU1-PA8-Pad41)") (class "Default")
      (node (ref "MCU1") (pin "41") (pinfunction "PA8_41") (pintype "bidirectional"))
    )
    (net (code "68") (name "unconnected-(MCU1-PA11-Pad44)") (class "Default")
      (node (ref "MCU1") (pin "44") (pinfunction "PA11_44") (pintype "bidirectional"))
    )
    (net (code "69") (name "unconnected-(MCU1-PA12-Pad45)") (class "Default")
      (node (ref "MCU1") (pin "45") (pinfunction "PA12_45") (pintype "bidirectional"))
    )
    (net (code "70") (name "unconnected-(MCU1-PB2-Pad28)") (class "Default")
      (node (ref "MCU1") (pin "28") (pinfunction "PB2_28") (pintype "bidirectional"))
    )
    (net (code "71") (name "unconnected-(MCU1-PB3-Pad55)") (class "Default")
      (node (ref "MCU1") (pin "55") (pinfunction "PB3_55") (pintype "bidirectional"))
    )
    (net (code "72") (name "unconnected-(MCU1-PB4-Pad56)") (class "Default")
      (node (ref "MCU1") (pin "56") (pinfunction "PB4_56") (pintype "bidirectional"))
    )
    (net (code "73") (name "unconnected-(MCU1-PB5-Pad57)") (class "Default")
      (node (ref "MCU1") (pin "57") (pinfunction "PB5_57") (pintype "bidirectional"))
    )
    (net (code "74") (name "unconnected-(MCU1-PB6-Pad58)") (class "Default")
      (node (ref "MCU1") (pin "58") (pinfunction "PB6_58") (pintype "bidirectional"))
    )
    (net (code "75") (name "unconnected-(MCU1-PB7-Pad59)") (class "Default")
      (node (ref "MCU1") (pin "59") (pinfunction "PB7_59") (pintype "bidirectional"))
    )
    (net (code "76") (name "unconnected-(MCU1-PB10-Pad29)") (class "Default")
      (node (ref "MCU1") (pin "29") (pinfunction "PB10_29") (pintype "bidirectional"))
    )
    (net (code "77") (name "unconnected-(MCU1-PB11-Pad30)") (class "Default")
      (node (ref "MCU1") (pin "30") (pinfunction "PB11_30") (pintype "bidirectional"))
    )
    (net (code "78") (name "unconnected-(MCU1-PB12-Pad33)") (class "Default")
      (node (ref "MCU1") (pin "33") (pinfunction "PB12_33") (pintype "bidirectional"))
    )
    (net (code "79") (name "unconnected-(MCU1-PB13-Pad34)") (class "Default")
      (node (ref "MCU1") (pin "34") (pinfunction "PB13_34") (pintype "bidirectional"))
    )
    (net (code "80") (name "unconnected-(MCU1-PB14-Pad35)") (class "Default")
      (node (ref "MCU1") (pin "35") (pinfunction "PB14_35") (pintype "bidirectional"))
    )
    (net (code "81") (name "unconnected-(MCU1-PB15-Pad36)") (class "Default")
      (node (ref "MCU1") (pin "36") (pinfunction "PB15_36") (pintype "bidirectional"))
    )
    (net (code "82") (name "unconnected-(MCU1-PC2-Pad10)") (class "Default")
      (node (ref "MCU1") (pin "10") (pinfunction "PC2_10") (pintype "bidirectional"))
    )
    (net (code "83") (name "unconnected-(MCU1-PC3-Pad11)") (class "Default")
      (node (ref "MCU1") (pin "11") (pinfunction "PC3_11") (pintype "bidirectional"))
    )
    (net (code "84") (name "unconnected-(MCU1-PC4-Pad24)") (class "Default")
      (node (ref "MCU1") (pin "24") (pinfunction "PC4_24") (pintype "bidirectional"))
    )
    (net (code "85") (name "unconnected-(MCU1-PC5-Pad25)") (class "Default")
      (node (ref "MCU1") (pin "25") (pinfunction "PC5_25") (pintype "bidirectional"))
    )
    (net (code "86") (name "unconnected-(MCU1-PC6-Pad37)") (class "Default")
      (node (ref "MCU1") (pin "37") (pinfunction "PC6_37") (pintype "bidirectional"))
    )
    (net (code "87") (name "unconnected-(MCU1-PC7-Pad38)") (class "Default")
      (node (ref "MCU1") (pin "38") (pinfunction "PC7_38") (pintype "bidirectional"))
    )
    (net (code "88") (name "unconnected-(MCU1-PC8-Pad39)") (class "Default")
      (node (ref "MCU1") (pin "39") (pinfunction "PC8_39") (pintype "bidirectional"))
    )
    (net (code "89") (name "unconnected-(MCU1-PC9-Pad40)") (class "Default")
      (node (ref "MCU1") (pin "40") (pinfunction "PC9_40") (pintype "bidirectional"))
    )
    (net (code "90") (name "unconnected-(MCU1-PC10-Pad51)") (class "Default")
      (node (ref "MCU1") (pin "51") (pinfunction "PC10_51") (pintype "bidirectional"))
    )
    (net (code "91") (name "unconnected-(MCU1-PC11-Pad52)") (class "Default")
      (node (ref "MCU1") (pin "52") (pinfunction "PC11_52") (pintype "bidirectional"))
    )
    (net (code "92") (name "unconnected-(MCU1-PC12-Pad53)") (class "Default")
      (node (ref "MCU1") (pin "53") (pinfunction "PC12_53") (pintype "bidirectional"))
    )
    (net (code "93") (name "unconnected-(MCU1-PC13-Pad2)") (class "Default")
      (node (ref "MCU1") (pin "2") (pinfunction "PC13_2") (pintype "bidirectional"))
    )
    (net (code "94") (name "unconnected-(MCU1-PC14{slash}OSC32_IN-Pad3)") (class "Default")
      (node (ref "MCU1") (pin "3") (pinfunction "PC14/OSC32_IN_3") (pintype "bidirectional"))
    )
    (net (code "95") (name "unconnected-(MCU1-PC15{slash}OSC32_OUT-Pad4)") (class "Default")
      (node (ref "MCU1") (pin "4") (pinfunction "PC15/OSC32_OUT_4") (pintype "bidirectional"))
    )
    (net (code "96") (name "unconnected-(MCU1-PF0{slash}OSC_IN-Pad5)") (class "Default")
      (node (ref "MCU1") (pin "5") (pinfunction "PF0/OSC_IN_5") (pintype "bidirectional"))
    )
    (net (code "97") (name "unconnected-(MCU1-PF1{slash}OSC_OUT-Pad6)") (class "Default")
      (node (ref "MCU1") (pin "6") (pinfunction "PF1/OSC_OUT_6") (pintype "bidirectional"))
    )
    (net (code "98") (name "unconnected-(MCU1-PF4-Pad18)") (class "Default")
      (node (ref "MCU1") (pin "18") (pinfunction "PF4_18") (pintype "bidirectional"))
    )
    (net (code "99") (name "unconnected-(MCU1-PF5-Pad19)") (class "Default")
      (node (ref "MCU1") (pin "19") (pinfunction "PF5_19") (pintype "bidirectional"))
    )
    (net (code "100") (name "unconnected-(MCU1-PF6-Pad47)") (class "Default")
      (node (ref "MCU1") (pin "47") (pinfunction "PF6_47") (pintype "bidirectional"))
    )
    (net (code "101") (name "unconnected-(MCU1-PF7-Pad48)") (class "Default")
      (node (ref "MCU1") (pin "48") (pinfunction "PF7_48") (pintype "bidirectional"))
    )
    (net (code "102") (name "unconnected-(U1-Ctrl-Pad3)") (class "Default")
      (node (ref "U1") (pin "3") (pinfunction "Ctrl_3") (pintype "passive+no_connect"))
    )
    (net (code "103") (name "unconnected-(U10-SCL5-Pad20)") (class "Default")
      (node (ref "U10") (pin "20") (pinfunction "SCL5_20") (pintype "output"))
    )
    (net (code "104") (name "unconnected-(U10-SCL6-Pad22)") (class "Default")
      (node (ref "U10") (pin "22") (pinfunction "SCL6_22") (pintype "output"))
    )
    (net (code "105") (name "unconnected-(U10-SCL7-Pad24)") (class "Default")
      (node (ref "U10") (pin "24") (pinfunction "SCL7_24") (pintype "output"))
    )
    (net (code "106") (name "unconnected-(U10-SDA5-Pad19)") (class "Default")
      (node (ref "U10") (pin "19") (pinfunction "SDA5_19") (pintype "bidirectional"))
    )
    (net (code "107") (name "unconnected-(U10-SDA6-Pad21)") (class "Default")
      (node (ref "U10") (pin "21") (pinfunction "SDA6_21") (pintype "bidirectional"))
    )
    (net (code "108") (name "unconnected-(U10-SDA7-Pad23)") (class "Default")
      (node (ref "U10") (pin "23") (pinfunction "SDA7_23") (pintype "bidirectional"))
    )
  )
)
